# rapidshark-dart-detector-mk-2_0.net
KiCad netlist of a schematic drawn in EAGLE
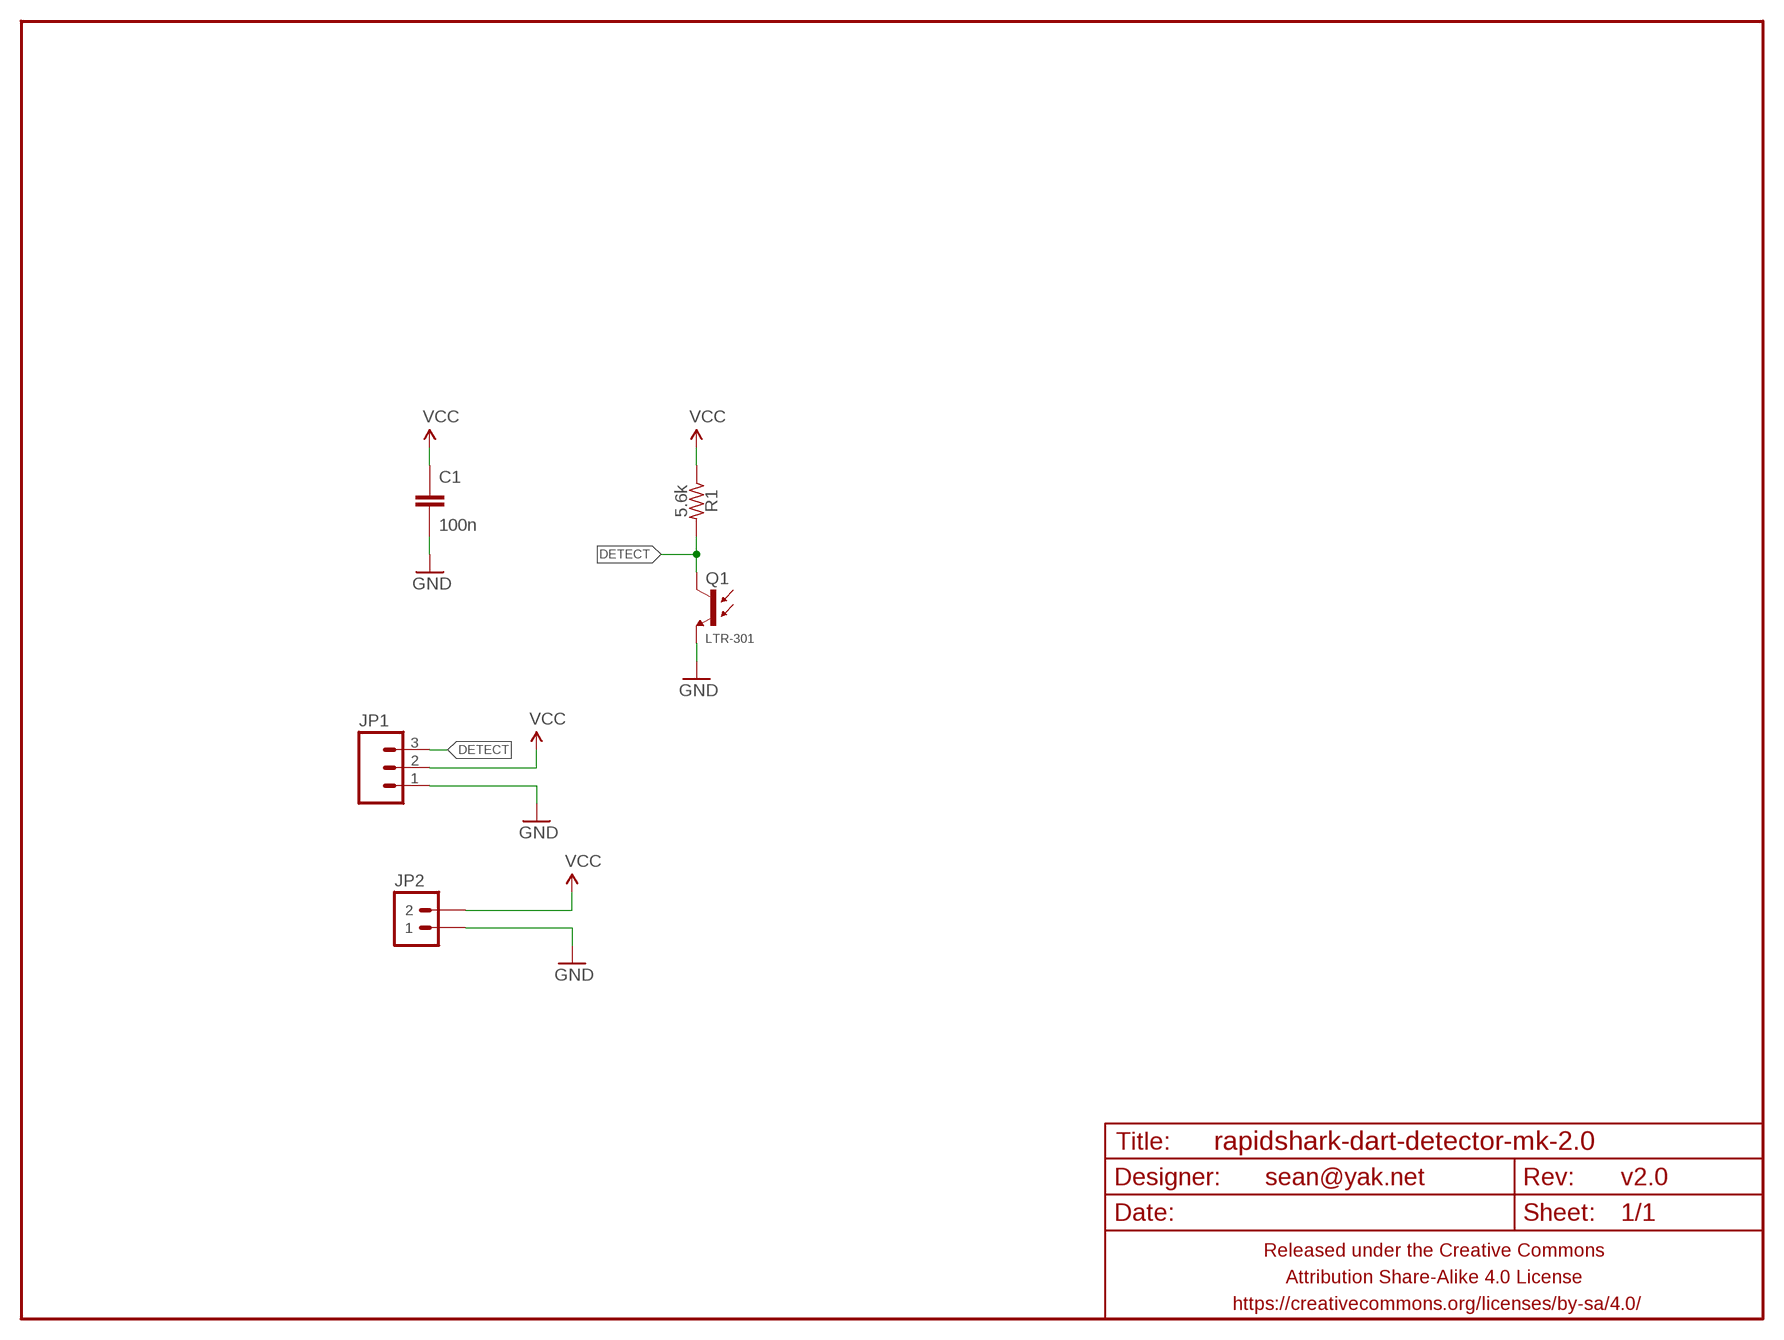
[diagram p0: schematic, sheet 1]

(export (version "E")
  (design (tool "Eeschema 10.0.6"))
  (components
    (comp (ref "C1")
      (value "100n")
      (footprint "eagle-import:C025-024X044")
      (libsource (lib "eagle-import") (part "CAPACITOR-CERAMIC025-024X044"))
    )
    (comp (ref "FRAME1")
      (value "FRAME-LETTERNO_PACKAGE")
      (footprint "eagle-import:DUMMY")
      (fields (field (name "DESIGNER") "sean@yak.net") (field (name "VERSION") "v2.0"))
      (libsource (lib "eagle-import") (part "FRAME-LETTERNO_PACKAGE"))
    )
    (comp (ref "JP1")
      (value "M03JST-PTH")
      (footprint "eagle-import:JST-3-PH-RA-PTH")
      (libsource (lib "eagle-import") (part "M03JST-PTH"))
    )
    (comp (ref "JP2")
      (value "M02JST-PTH-RA-R+")
      (footprint "eagle-import:JST-2-PH-RA-PTH-R+")
      (libsource (lib "eagle-import") (part "M02JST-PTH-RA-R+"))
    )
    (comp (ref "Q1")
      (value "LTR-301")
      (footprint "eagle-import:LED-2.54MM-SIDE")
      (libsource (lib "eagle-import") (part "PHOTOTRANSISTOR2.54MM-SIDE"))
    )
    (comp (ref "R1")
      (value "5.6k")
      (footprint "eagle-import:RESISTOR-AXIAL-PTH-5.08MM")
      (libsource (lib "eagle-import") (part "RESISTORPTH-AXIAL-5.08MM"))
    )
  )
  (nets
    (net (code "1") (name "DETECT") (class "Default")
      (node (ref "JP1") (pin "3") (pinfunction "3_3") (pintype "passive"))
      (node (ref "Q1") (pin "A") (pinfunction "C_A") (pintype "bidirectional"))
      (node (ref "R1") (pin "P$2") (pinfunction "2_P$2") (pintype "passive"))
    )
    (net (code "2") (name "GND") (class "Default")
      (node (ref "C1") (pin "2") (pinfunction "2_2") (pintype "passive"))
      (node (ref "JP1") (pin "1") (pinfunction "1_1") (pintype "passive"))
      (node (ref "JP2") (pin "1") (pinfunction "1_1") (pintype "passive"))
      (node (ref "Q1") (pin "K") (pinfunction "E_K") (pintype "bidirectional"))
    )
    (net (code "3") (name "VCC") (class "Default")
      (node (ref "C1") (pin "1") (pinfunction "1_1") (pintype "passive"))
      (node (ref "JP1") (pin "2") (pinfunction "2_2") (pintype "passive"))
      (node (ref "JP2") (pin "2") (pinfunction "2_2") (pintype "passive"))
      (node (ref "R1") (pin "P$1") (pinfunction "1_P$1") (pintype "passive"))
    )
  )
)
